# Thermostat.net
KiCad netlist of a schematic drawn in Altium Designer
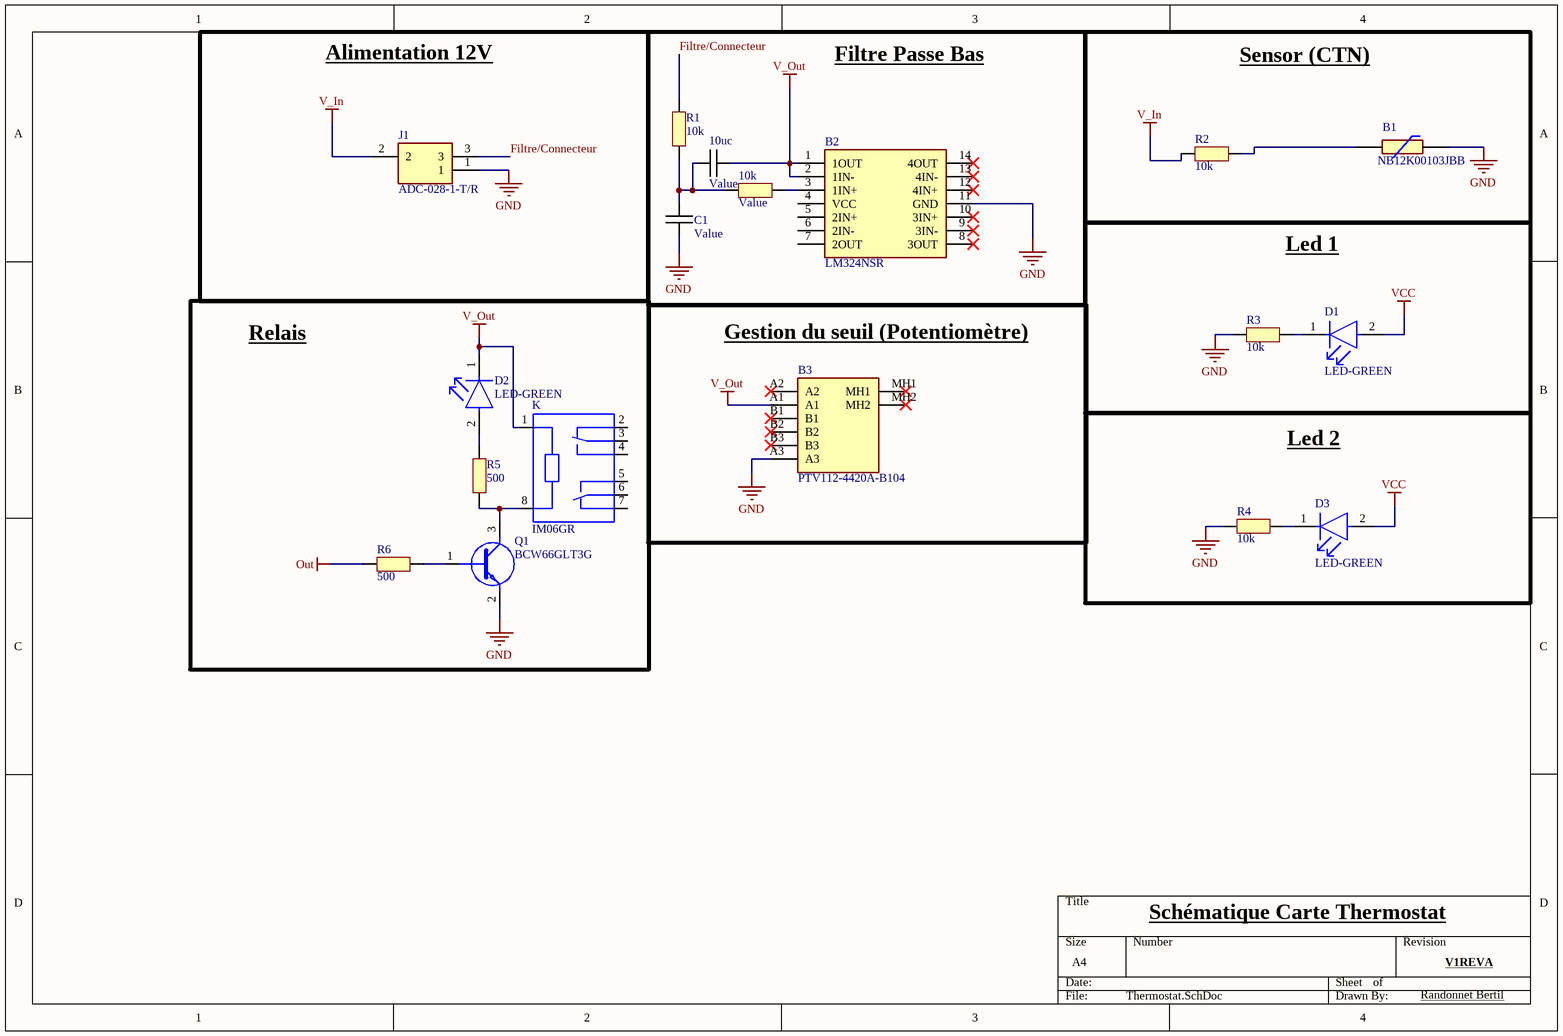
[diagram p0: Thermostat.SchDoc]

(export (version "E")
  (design (tool "Eeschema 10.0.6"))
  (components
    (comp (ref "10k") (value "Value") (footprint "RESC1005X06N") (libsource (lib "") (part "Resistor_2")))
    (comp (ref "10uc")
      (value "Value")
      (footprint "CAPC1005X06N")
      (libsource (lib "Schlib1") (part "Capacitor"))
    )
    (comp (ref "B1")
      (value "NB12K00103JBB")
      (footprint "RESC2212X50N")
      (description "NTC SMD Thermistor, NB12K, 10K, 5% AVX 10k 0805 Protection NTC Thermistor, 5s, 2 x 1.25 x 1.3mm")
      (fields (field (name "MOUSER PART NUMBER") "581-NB12K00103JBB"))
      (libsource (lib "SCHLibrary") (part "NB12K00103JBB"))
    )
    (comp (ref "B2")
      (value "LM324NSR")
      (footprint "SOIC127P780X200-14N")
      (description "Quadruple Operational Amplifier")
      (fields (field (name "MOUSER PART NUMBER") "595-LM324NSR"))
      (libsource (lib "Schlib1") (part "LM324NSR"))
    )
    (comp (ref "B3")
      (value "PTV112-4420A-B104")
      (footprint "PTV1124420AB104")
      (description "Potentiometers PANEL CONTROL 100kOhm")
      (fields (field (name "MOUSER PART NUMBER") "652-PTV1124420AB104"))
      (libsource (lib "Schlib1") (part "PTV112-4420A-B104"))
    )
    (comp (ref "C1")
      (value "Value")
      (footprint "CAPC1005X06N")
      (libsource (lib "Schlib1") (part "Capacitor"))
    )
    (comp (ref "D1")
      (value "LED-GREEN")
      (footprint "SMD-1608-LED")
      (description "LED GREEN CLEAR CHIP SMD LTST-C190GKT")
      (fields (field (name "VOLTAGE") "2V"))
      (libsource (lib "Schlib1") (part "LED-GREEN"))
    )
    (comp (ref "D2")
      (value "LED-GREEN")
      (footprint "SMD-1608-LED")
      (description "LED GREEN CLEAR CHIP SMD LTST-C190GKT")
      (fields (field (name "VOLTAGE") "2V"))
      (libsource (lib "Schlib1") (part "LED-GREEN"))
    )
    (comp (ref "D3")
      (value "LED-GREEN")
      (footprint "SMD-1608-LED")
      (description "LED GREEN CLEAR CHIP SMD LTST-C190GKT")
      (fields (field (name "VOLTAGE") "2V"))
      (libsource (lib "Schlib1") (part "LED-GREEN"))
    )
    (comp (ref "J1")
      (value "ADC-028-1-T/R")
      (footprint "PJ1021SMTTR")
      (description "Connecteurs d'alimentation continue DC POWER JACK 2MM PIN TYPE 028")
      (fields (field (name "MOUSER PART NUMBER") "737-ADC-028-1-T/R"))
      (libsource (lib "Schlib1") (part "ADC-028-1-T/R"))
    )
    (comp (ref "K")
      (value "IM06GR")
      (footprint "RELAY_IM06GR")
      (description "Electromechanical Relay 12VDC 1.029KOhm 2A DPDT _10x7.5x5.65_mm SMD Signal Relay")
      (fields (field (name "MF") "TE Connectivity"))
      (libsource (lib "Schlib1") (part "IM06GR"))
    )
    (comp (ref "Q1")
      (value "BCW66GLT3G")
      (footprint "SOT96P237X111-3N")
      (description "NPN Bipolar Transistor")
      (fields (field (name "MOUSER PART NUMBER") "863-BCW66GLT3G"))
      (libsource (lib "Schlib1") (part "BCW66GLT3G"))
    )
    (comp (ref "R1") (value "10k") (footprint "RESC1005X06N") (libsource (lib "Schlib1") (part "Resistor")))
    (comp (ref "R2")
      (value "10k")
      (footprint "RESC1005X06N")
      (libsource (lib "SCHLibrary") (part "Resistor"))
    )
    (comp (ref "R3") (value "10k") (footprint "RESC1005X06N") (libsource (lib "") (part "Resistor_1")))
    (comp (ref "R4") (value "10k") (footprint "RESC1005X06N") (libsource (lib "") (part "Resistor_1")))
    (comp (ref "R5") (value "500") (footprint "RESC1005X06N") (libsource (lib "Schlib1") (part "Resistor")))
    (comp (ref "R6") (value "500") (footprint "RESC1005X06N") (libsource (lib "") (part "Resistor_1")))
  )
  (nets
    (net (code "1") (name "/Filtre{slash}Connecteur") (class "Default")
      (node (ref "J1") (pin "3") (pinfunction "3_3") (pintype "passive"))
      (node (ref "R1") (pin "2") (pinfunction "2_2") (pintype "passive"))
    )
    (net (code "2") (name "GND") (class "Default")
      (node (ref "B1") (pin "1") (pinfunction "1_1") (pintype "passive"))
      (node (ref "B2") (pin "11") (pinfunction "GND_11") (pintype "passive"))
      (node (ref "B3") (pin "A3") (pinfunction "A3_A3") (pintype "passive"))
      (node (ref "C1") (pin "2") (pinfunction "2_2") (pintype "passive"))
      (node (ref "J1") (pin "1") (pinfunction "1_1") (pintype "passive"))
      (node (ref "Q1") (pin "2") (pinfunction "E_2") (pintype "passive"))
      (node (ref "R3") (pin "2") (pinfunction "2_2") (pintype "passive"))
      (node (ref "R4") (pin "2") (pinfunction "2_2") (pintype "passive"))
    )
    (net (code "3") (name "Net-(10k-Pad1)") (class "Default")
      (node (ref "10k") (pin "1") (pinfunction "1_1") (pintype "passive"))
      (node (ref "10uc") (pin "1") (pinfunction "1_1") (pintype "passive"))
      (node (ref "C1") (pin "1") (pinfunction "1_1") (pintype "passive"))
      (node (ref "R1") (pin "1") (pinfunction "1_1") (pintype "passive"))
    )
    (net (code "4") (name "Net-(B1-Pad2)") (class "Default")
      (node (ref "B1") (pin "2") (pinfunction "2_2") (pintype "passive"))
      (node (ref "R2") (pin "2") (pinfunction "2_2") (pintype "passive"))
    )
    (net (code "5") (name "Net-(B2-1IN+)") (class "Default")
      (node (ref "10k") (pin "2") (pinfunction "2_2") (pintype "passive"))
      (node (ref "B2") (pin "3") (pinfunction "1IN+_3") (pintype "passive"))
    )
    (net (code "6") (name "Net-(D1-C)") (class "Default")
      (node (ref "D1") (pin "1") (pinfunction "C_1") (pintype "passive"))
      (node (ref "R3") (pin "1") (pinfunction "1_1") (pintype "passive"))
    )
    (net (code "7") (name "Net-(D2-A)") (class "Default")
      (node (ref "D2") (pin "2") (pinfunction "A_2") (pintype "passive"))
      (node (ref "R5") (pin "2") (pinfunction "2_2") (pintype "passive"))
    )
    (net (code "8") (name "Net-(D3-C)") (class "Default")
      (node (ref "D3") (pin "1") (pinfunction "C_1") (pintype "passive"))
      (node (ref "R4") (pin "1") (pinfunction "1_1") (pintype "passive"))
    )
    (net (code "9") (name "Net-(Q1-B)") (class "Default")
      (node (ref "Q1") (pin "1") (pinfunction "B_1") (pintype "passive"))
      (node (ref "R6") (pin "1") (pinfunction "1_1") (pintype "passive"))
    )
    (net (code "10") (name "Net-(Q1-C)") (class "Default")
      (node (ref "K") (pin "8") (pinfunction "8_8") (pintype "passive"))
      (node (ref "Q1") (pin "3") (pinfunction "C_3") (pintype "passive"))
      (node (ref "R5") (pin "1") (pinfunction "1_1") (pintype "passive"))
    )
    (net (code "11") (name "Out") (class "Default")
      (node (ref "R6") (pin "2") (pinfunction "2_2") (pintype "passive"))
    )
    (net (code "12") (name "VCC") (class "Default")
      (node (ref "D1") (pin "2") (pinfunction "A_2") (pintype "passive"))
      (node (ref "D3") (pin "2") (pinfunction "A_2") (pintype "passive"))
    )
    (net (code "13") (name "V_In") (class "Default")
      (node (ref "J1") (pin "2") (pinfunction "2_2") (pintype "passive"))
      (node (ref "R2") (pin "1") (pinfunction "1_1") (pintype "passive"))
    )
    (net (code "14") (name "V_Out") (class "Default")
      (node (ref "10uc") (pin "2") (pinfunction "2_2") (pintype "passive"))
      (node (ref "B2") (pin "1") (pinfunction "1OUT_1") (pintype "passive"))
      (node (ref "B2") (pin "2") (pinfunction "1IN-_2") (pintype "passive"))
      (node (ref "B3") (pin "A1") (pinfunction "A1_A1") (pintype "passive"))
      (node (ref "D2") (pin "1") (pinfunction "C_1") (pintype "passive"))
      (node (ref "K") (pin "1") (pinfunction "1_1") (pintype "passive"))
    )
    (net (code "15") (name "unconnected-(B2-2IN+-Pad5)") (class "Default")
      (node (ref "B2") (pin "5") (pinfunction "2IN+_5") (pintype "passive"))
    )
    (net (code "16") (name "unconnected-(B2-2IN--Pad6)") (class "Default")
      (node (ref "B2") (pin "6") (pinfunction "2IN-_6") (pintype "passive"))
    )
    (net (code "17") (name "unconnected-(B2-2OUT-Pad7)") (class "Default")
      (node (ref "B2") (pin "7") (pinfunction "2OUT_7") (pintype "passive"))
    )
    (net (code "18") (name "unconnected-(B2-3IN+-Pad10)") (class "Default")
      (node (ref "B2") (pin "10") (pinfunction "3IN+_10") (pintype "passive+no_connect"))
    )
    (net (code "19") (name "unconnected-(B2-3IN--Pad9)") (class "Default")
      (node (ref "B2") (pin "9") (pinfunction "3IN-_9") (pintype "passive+no_connect"))
    )
    (net (code "20") (name "unconnected-(B2-3OUT-Pad8)") (class "Default")
      (node (ref "B2") (pin "8") (pinfunction "3OUT_8") (pintype "passive+no_connect"))
    )
    (net (code "21") (name "unconnected-(B2-4IN+-Pad12)") (class "Default")
      (node (ref "B2") (pin "12") (pinfunction "4IN+_12") (pintype "passive+no_connect"))
    )
    (net (code "22") (name "unconnected-(B2-4IN--Pad13)") (class "Default")
      (node (ref "B2") (pin "13") (pinfunction "4IN-_13") (pintype "passive+no_connect"))
    )
    (net (code "23") (name "unconnected-(B2-4OUT-Pad14)") (class "Default")
      (node (ref "B2") (pin "14") (pinfunction "4OUT_14") (pintype "passive+no_connect"))
    )
    (net (code "24") (name "unconnected-(B2-VCC-Pad4)") (class "Default")
      (node (ref "B2") (pin "4") (pinfunction "VCC_4") (pintype "passive"))
    )
    (net (code "25") (name "unconnected-(B3-PadA2)") (class "Default")
      (node (ref "B3") (pin "A2") (pinfunction "A2_A2") (pintype "passive+no_connect"))
    )
    (net (code "26") (name "unconnected-(B3-PadB1)") (class "Default")
      (node (ref "B3") (pin "B1") (pinfunction "B1_B1") (pintype "passive+no_connect"))
    )
    (net (code "27") (name "unconnected-(B3-PadB2)") (class "Default")
      (node (ref "B3") (pin "B2") (pinfunction "B2_B2") (pintype "passive+no_connect"))
    )
    (net (code "28") (name "unconnected-(B3-PadB3)") (class "Default")
      (node (ref "B3") (pin "B3") (pinfunction "B3_B3") (pintype "passive+no_connect"))
    )
    (net (code "29") (name "unconnected-(B3-PadMH1)") (class "Default")
      (node (ref "B3") (pin "MH1") (pinfunction "MH1_MH1") (pintype "passive+no_connect"))
    )
    (net (code "30") (name "unconnected-(B3-PadMH2)") (class "Default")
      (node (ref "B3") (pin "MH2") (pinfunction "MH2_MH2") (pintype "passive+no_connect"))
    )
    (net (code "31") (name "unconnected-(K-Pad2)") (class "Default")
      (node (ref "K") (pin "2") (pinfunction "2_2") (pintype "passive"))
    )
    (net (code "32") (name "unconnected-(K-Pad3)") (class "Default")
      (node (ref "K") (pin "3") (pinfunction "3_3") (pintype "passive"))
    )
    (net (code "33") (name "unconnected-(K-Pad4)") (class "Default")
      (node (ref "K") (pin "4") (pinfunction "4_4") (pintype "passive"))
    )
    (net (code "34") (name "unconnected-(K-Pad5)") (class "Default")
      (node (ref "K") (pin "5") (pinfunction "5_5") (pintype "passive"))
    )
    (net (code "35") (name "unconnected-(K-Pad6)") (class "Default")
      (node (ref "K") (pin "6") (pinfunction "6_6") (pintype "passive"))
    )
    (net (code "36") (name "unconnected-(K-Pad7)") (class "Default")
      (node (ref "K") (pin "7") (pinfunction "7_7") (pintype "passive"))
    )
  )
)
